# Sheet_3.net
KiCad netlist of a schematic drawn in Altium Designer
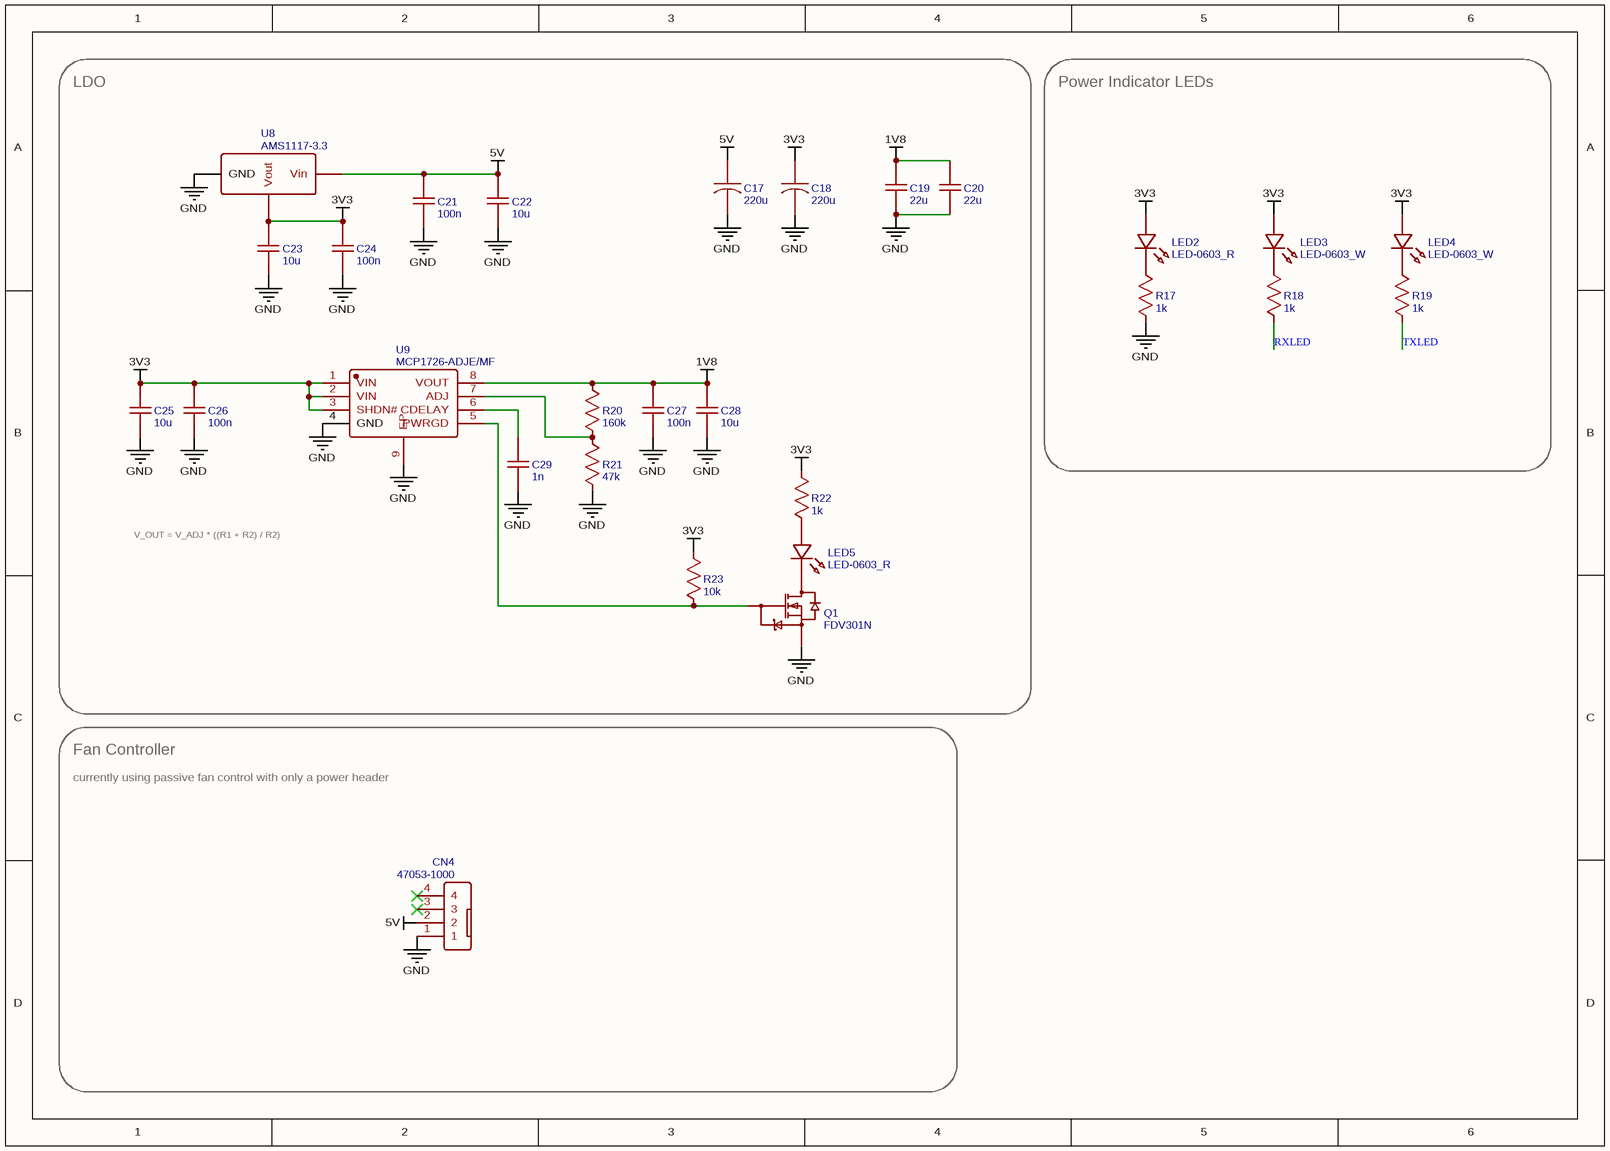
[diagram p0: Sheet_3.schdoc]

(export (version "E")
  (design (tool "Eeschema 10.0.6"))
  (components
    (comp (ref "C17")
      (value "220u")
      (footprint "CAPPR5.0-D6.3_L6.6_W6.6")
      (fields
        (field (name "BOM_SUPPLIER PART") "C131157")
        (field (name "BOM_MANUFACTURER PART") "CK1A221M-CRE54")
      )
      (libsource (lib "altium-import") (part "root_3_220u_"))
    )
    (comp (ref "C18")
      (value "220u")
      (footprint "CAPPR5.0-D6.3_L6.6_W6.6")
      (fields
        (field (name "BOM_SUPPLIER PART") "C131157")
        (field (name "BOM_MANUFACTURER PART") "CK1A221M-CRE54")
      )
      (libsource (lib "altium-import") (part "root_3_220u_"))
    )
    (comp (ref "C19")
      (value "22u")
      (footprint "CAPA-1206")
      (fields
        (field (name "BOM_SUPPLIER PART") "C12891")
        (field (name "BOM_MANUFACTURER PART") "CL31A226KAHNNNE")
      )
      (libsource (lib "altium-import") (part "root_1_22u_"))
    )
    (comp (ref "C20")
      (value "22u")
      (footprint "CAPA-1206")
      (fields
        (field (name "BOM_SUPPLIER PART") "C12891")
        (field (name "BOM_MANUFACTURER PART") "CL31A226KAHNNNE")
      )
      (libsource (lib "altium-import") (part "root_1_22u_"))
    )
    (comp (ref "C21")
      (value "100n")
      (footprint "CAPA-0402")
      (fields
        (field (name "BOM_SUPPLIER PART") "C307331")
        (field (name "BOM_MANUFACTURER PART") "CL05B104KB54PNC")
      )
      (libsource (lib "altium-import") (part "root_1_100n_"))
    )
    (comp (ref "C22")
      (value "10u")
      (footprint "CAPA-0402")
      (fields
        (field (name "BOM_SUPPLIER PART") "C87148")
        (field (name "BOM_MANUFACTURER PART") "JMK105CBJ106MV-F")
      )
      (libsource (lib "altium-import") (part "root_1_10u_"))
    )
    (comp (ref "C23")
      (value "10u")
      (footprint "CAPA-0402")
      (fields
        (field (name "BOM_SUPPLIER PART") "C87148")
        (field (name "BOM_MANUFACTURER PART") "JMK105CBJ106MV-F")
      )
      (libsource (lib "altium-import") (part "root_1_10u_"))
    )
    (comp (ref "C24")
      (value "100n")
      (footprint "CAPA-0402")
      (fields
        (field (name "BOM_SUPPLIER PART") "C307331")
        (field (name "BOM_MANUFACTURER PART") "CL05B104KB54PNC")
      )
      (libsource (lib "altium-import") (part "root_1_100n_"))
    )
    (comp (ref "C25")
      (value "10u")
      (footprint "CAPA-0402")
      (fields
        (field (name "BOM_SUPPLIER PART") "C87148")
        (field (name "BOM_MANUFACTURER PART") "JMK105CBJ106MV-F")
      )
      (libsource (lib "altium-import") (part "root_1_10u_"))
    )
    (comp (ref "C26")
      (value "100n")
      (footprint "CAPA-0402")
      (fields
        (field (name "BOM_SUPPLIER PART") "C307331")
        (field (name "BOM_MANUFACTURER PART") "CL05B104KB54PNC")
      )
      (libsource (lib "altium-import") (part "root_1_100n_"))
    )
    (comp (ref "C27")
      (value "100n")
      (footprint "CAPA-0402")
      (fields
        (field (name "BOM_SUPPLIER PART") "C307331")
        (field (name "BOM_MANUFACTURER PART") "CL05B104KB54PNC")
      )
      (libsource (lib "altium-import") (part "root_1_100n_"))
    )
    (comp (ref "C28")
      (value "10u")
      (footprint "CAPA-0402")
      (fields
        (field (name "BOM_SUPPLIER PART") "C87148")
        (field (name "BOM_MANUFACTURER PART") "JMK105CBJ106MV-F")
      )
      (libsource (lib "altium-import") (part "root_1_10u_"))
    )
    (comp (ref "C29")
      (value "1n")
      (footprint "CAPA-0402")
      (fields
        (field (name "BOM_SUPPLIER PART") "C113780")
        (field (name "BOM_MANUFACTURER PART") "CC0402JRNPO9BN102")
      )
      (libsource (lib "altium-import") (part "root_1_1n_"))
    )
    (comp (ref "CN4")
      (value "47053-1000")
      (footprint "CONN-TH_47053-1000")
      (fields (field (name "BOM_SUPPLIER PART") "C240840") (field (name "BOM_MANUFACTURER PART") "470531000"))
      (libsource (lib "altium-import") (part "root_2_47053-1000_"))
    )
    (comp (ref "LED2")
      (value "LED-0603_R")
      (footprint "LED-0603")
      (fields
        (field (name "BOM_MANUFACTURER PART") "19-217/R6C-AL1M2VY/3T")
        (field (name "BOM_SUPPLIER PART") "C72044")
        (field (name "CONTRIBUTOR") "LCEDA_01")
      )
      (libsource (lib "altium-import") (part "root_3_LED-0603_R_"))
    )
    (comp (ref "LED3")
      (value "LED-0603_W")
      (footprint "LED-0603")
      (fields (field (name "BOM_MANUFACTURER PART") "LED White") (field (name "BOM_SUPPLIER PART") "C2290"))
      (libsource (lib "altium-import") (part "root_3_LED-0603_W_"))
    )
    (comp (ref "LED4")
      (value "LED-0603_W")
      (footprint "LED-0603")
      (fields (field (name "BOM_MANUFACTURER PART") "LED White") (field (name "BOM_SUPPLIER PART") "C2290"))
      (libsource (lib "altium-import") (part "root_3_LED-0603_W_"))
    )
    (comp (ref "LED5")
      (value "LED-0603_R")
      (footprint "LED-0603")
      (fields
        (field (name "BOM_MANUFACTURER PART") "19-217/R6C-AL1M2VY/3T")
        (field (name "BOM_SUPPLIER PART") "C72044")
        (field (name "CONTRIBUTOR") "LCEDA_01")
      )
      (libsource (lib "altium-import") (part "root_3_LED-0603_R_"))
    )
    (comp (ref "Q1")
      (value "FDV301N")
      (footprint "SOT-23_L2.9-W1.3-P1.90-LS2.4-BR")
      (fields (field (name "BOM_SUPPLIER PART") "C15310"))
      (libsource (lib "altium-import") (part "root_0_FDV301N_"))
    )
    (comp (ref "R17")
      (value "1k")
      (footprint "RES-0402")
      (fields
        (field (name "BOM_SUPPLIER PART") "C11702")
        (field (name "BOM_MANUFACTURER PART") "0402WGF1001TCE")
      )
      (libsource (lib "altium-import") (part "root_1_1k_"))
    )
    (comp (ref "R18")
      (value "1k")
      (footprint "RES-0402")
      (fields
        (field (name "BOM_SUPPLIER PART") "C11702")
        (field (name "BOM_MANUFACTURER PART") "0402WGF1001TCE")
      )
      (libsource (lib "altium-import") (part "root_1_1k_"))
    )
    (comp (ref "R19")
      (value "1k")
      (footprint "RES-0402")
      (fields
        (field (name "BOM_SUPPLIER PART") "C11702")
        (field (name "BOM_MANUFACTURER PART") "0402WGF1001TCE")
      )
      (libsource (lib "altium-import") (part "root_1_1k_"))
    )
    (comp (ref "R20")
      (value "160k")
      (footprint "RES-0402")
      (fields
        (field (name "BOM_SUPPLIER PART") "C25757")
        (field (name "BOM_MANUFACTURER PART") "0402WGF1603TCE")
      )
      (libsource (lib "altium-import") (part "root_1_160k_"))
    )
    (comp (ref "R21")
      (value "47k")
      (footprint "RES-0402")
      (fields
        (field (name "BOM_SUPPLIER PART") "C25792")
        (field (name "BOM_MANUFACTURER PART") "0402WGF4702TCE")
      )
      (libsource (lib "altium-import") (part "root_1_47k_"))
    )
    (comp (ref "R22")
      (value "1k")
      (footprint "RES-0402")
      (fields
        (field (name "BOM_SUPPLIER PART") "C11702")
        (field (name "BOM_MANUFACTURER PART") "0402WGF1001TCE")
      )
      (libsource (lib "altium-import") (part "root_1_1k_"))
    )
    (comp (ref "R23")
      (value "10k")
      (footprint "RES-0402")
      (fields
        (field (name "BOM_SUPPLIER PART") "C25744")
        (field (name "BOM_MANUFACTURER PART") "0402WGF1002TCE")
      )
      (libsource (lib "altium-import") (part "root_1_10k_"))
    )
    (comp (ref "U8")
      (value "AMS1117-3.3")
      (footprint "SOT-223_L6.5_W3.5_P2.30_BL")
      (fields (field (name "BOM_SUPPLIER PART") "C6186") (field (name "CONTRIBUTOR") "T-K-233"))
      (libsource (lib "altium-import") (part "root_0_AMS1117-3.3_"))
    )
    (comp (ref "U9")
      (value "MCP1726-ADJE/MF")
      (footprint "TDFN-8_L3.0-W3.0-P0.65-BL-EP")
      (fields (field (name "BOM_SUPPLIER PART") "C184287"))
      (libsource (lib "altium-import") (part "root_0_MCP1726-ADJE/MF_"))
    )
  )
  (nets
    (net (code "1") (name "/RXLED") (class "Default")
      (node (ref "R18") (pin "1") (pinfunction "1_1") (pintype "passive"))
    )
    (net (code "2") (name "/TXLED") (class "Default")
      (node (ref "R19") (pin "1") (pinfunction "1_1") (pintype "passive"))
    )
    (net (code "3") (name "1V8") (class "Default")
      (node (ref "C19") (pin "2") (pinfunction "2_2") (pintype "passive"))
      (node (ref "C20") (pin "2") (pinfunction "2_2") (pintype "passive"))
      (node (ref "C27") (pin "2") (pinfunction "2_2") (pintype "passive"))
      (node (ref "C28") (pin "2") (pinfunction "2_2") (pintype "passive"))
      (node (ref "R20") (pin "2") (pinfunction "2_2") (pintype "passive"))
      (node (ref "U9") (pin "8") (pinfunction "VOUT_8") (pintype "passive"))
    )
    (net (code "4") (name "3V3") (class "Default")
      (node (ref "C18") (pin "1") (pinfunction "1_1") (pintype "passive"))
      (node (ref "C23") (pin "2") (pinfunction "2_2") (pintype "passive"))
      (node (ref "C24") (pin "2") (pinfunction "2_2") (pintype "passive"))
      (node (ref "C25") (pin "2") (pinfunction "2_2") (pintype "passive"))
      (node (ref "C26") (pin "2") (pinfunction "2_2") (pintype "passive"))
      (node (ref "LED2") (pin "1") (pinfunction "1_1") (pintype "passive"))
      (node (ref "LED3") (pin "1") (pinfunction "1_1") (pintype "passive"))
      (node (ref "LED4") (pin "1") (pinfunction "1_1") (pintype "passive"))
      (node (ref "R22") (pin "2") (pinfunction "2_2") (pintype "passive"))
      (node (ref "R23") (pin "2") (pinfunction "2_2") (pintype "passive"))
      (node (ref "U8") (pin "2") (pinfunction "Vout_2") (pintype "passive"))
      (node (ref "U9") (pin "1") (pinfunction "VIN_1") (pintype "passive"))
      (node (ref "U9") (pin "2") (pinfunction "VIN_2") (pintype "passive"))
      (node (ref "U9") (pin "3") (pinfunction "SHDN#_3") (pintype "passive"))
    )
    (net (code "5") (name "5V") (class "Default")
      (node (ref "C17") (pin "1") (pinfunction "1_1") (pintype "passive"))
      (node (ref "C21") (pin "2") (pinfunction "2_2") (pintype "passive"))
      (node (ref "C22") (pin "2") (pinfunction "2_2") (pintype "passive"))
      (node (ref "CN4") (pin "2") (pinfunction "2_2") (pintype "passive"))
      (node (ref "U8") (pin "3") (pinfunction "Vin_3") (pintype "passive"))
    )
    (net (code "6") (name "GND") (class "Default")
      (node (ref "C17") (pin "2") (pinfunction "2_2") (pintype "passive"))
      (node (ref "C18") (pin "2") (pinfunction "2_2") (pintype "passive"))
      (node (ref "C19") (pin "1") (pinfunction "1_1") (pintype "passive"))
      (node (ref "C20") (pin "1") (pinfunction "1_1") (pintype "passive"))
      (node (ref "C21") (pin "1") (pinfunction "1_1") (pintype "passive"))
      (node (ref "C22") (pin "1") (pinfunction "1_1") (pintype "passive"))
      (node (ref "C23") (pin "1") (pinfunction "1_1") (pintype "passive"))
      (node (ref "C24") (pin "1") (pinfunction "1_1") (pintype "passive"))
      (node (ref "C25") (pin "1") (pinfunction "1_1") (pintype "passive"))
      (node (ref "C26") (pin "1") (pinfunction "1_1") (pintype "passive"))
      (node (ref "C27") (pin "1") (pinfunction "1_1") (pintype "passive"))
      (node (ref "C28") (pin "1") (pinfunction "1_1") (pintype "passive"))
      (node (ref "C29") (pin "1") (pinfunction "1_1") (pintype "passive"))
      (node (ref "CN4") (pin "1") (pinfunction "1_1") (pintype "passive"))
      (node (ref "Q1") (pin "2") (pinfunction "S_2") (pintype "passive"))
      (node (ref "R17") (pin "1") (pinfunction "1_1") (pintype "passive"))
      (node (ref "R21") (pin "1") (pinfunction "1_1") (pintype "passive"))
      (node (ref "U8") (pin "1") (pinfunction "GND_1") (pintype "passive"))
      (node (ref "U9") (pin "4") (pinfunction "GND_4") (pintype "passive"))
      (node (ref "U9") (pin "9") (pinfunction "EP_9") (pintype "passive"))
    )
    (net (code "7") (name "Net-(LED2-Pad2)") (class "Default")
      (node (ref "LED2") (pin "2") (pinfunction "2_2") (pintype "passive"))
      (node (ref "R17") (pin "2") (pinfunction "2_2") (pintype "passive"))
    )
    (net (code "8") (name "Net-(LED3-Pad2)") (class "Default")
      (node (ref "LED3") (pin "2") (pinfunction "2_2") (pintype "passive"))
      (node (ref "R18") (pin "2") (pinfunction "2_2") (pintype "passive"))
    )
    (net (code "9") (name "Net-(LED4-Pad2)") (class "Default")
      (node (ref "LED4") (pin "2") (pinfunction "2_2") (pintype "passive"))
      (node (ref "R19") (pin "2") (pinfunction "2_2") (pintype "passive"))
    )
    (net (code "10") (name "Net-(LED5-Pad1)") (class "Default")
      (node (ref "LED5") (pin "1") (pinfunction "1_1") (pintype "passive"))
      (node (ref "R22") (pin "1") (pinfunction "1_1") (pintype "passive"))
    )
    (net (code "11") (name "Net-(Q1-D)") (class "Default")
      (node (ref "LED5") (pin "2") (pinfunction "2_2") (pintype "passive"))
      (node (ref "Q1") (pin "3") (pinfunction "D_3") (pintype "passive"))
    )
    (net (code "12") (name "Net-(Q1-G)") (class "Default")
      (node (ref "Q1") (pin "1") (pinfunction "G_1") (pintype "passive"))
      (node (ref "R23") (pin "1") (pinfunction "1_1") (pintype "passive"))
      (node (ref "U9") (pin "5") (pinfunction "PWRGD_5") (pintype "passive"))
    )
    (net (code "13") (name "Net-(U9-ADJ)") (class "Default")
      (node (ref "R20") (pin "1") (pinfunction "1_1") (pintype "passive"))
      (node (ref "R21") (pin "2") (pinfunction "2_2") (pintype "passive"))
      (node (ref "U9") (pin "7") (pinfunction "ADJ_7") (pintype "passive"))
    )
    (net (code "14") (name "Net-(U9-CDELAY)") (class "Default")
      (node (ref "C29") (pin "2") (pinfunction "2_2") (pintype "passive"))
      (node (ref "U9") (pin "6") (pinfunction "CDELAY_6") (pintype "passive"))
    )
    (net (code "15") (name "unconnected-(CN4-Pad3)") (class "Default")
      (node (ref "CN4") (pin "3") (pinfunction "3_3") (pintype "passive+no_connect"))
    )
    (net (code "16") (name "unconnected-(CN4-Pad4)") (class "Default")
      (node (ref "CN4") (pin "4") (pinfunction "4_4") (pintype "passive+no_connect"))
    )
  )
)
